# AD9851.net
KiCad netlist of a schematic drawn in Altium Designer
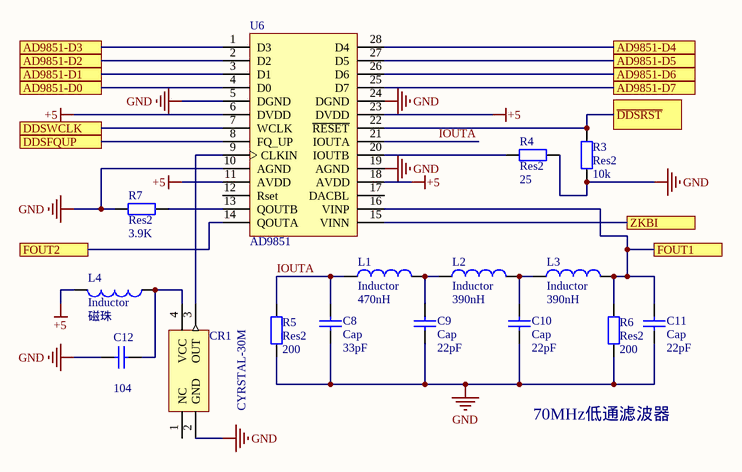
[diagram p0: AD9851电路.SchDoc]

(export (version "E")
  (design (tool "Eeschema 10.0.6"))
  (components
    (comp (ref "C8")
      (value "Cap")
      (footprint "C0805")
      (description "Capacitor")
      (fields (field (name "ALTIUM_VALUE") "33pF") (field (name "PUBLISHER") "Altium Limited"))
      (libsource (lib "基于SMT32的DDS信号源原理图库") (part "Cap"))
    )
    (comp (ref "C9")
      (value "Cap")
      (footprint "C0805")
      (description "Capacitor")
      (fields (field (name "ALTIUM_VALUE") "22pF") (field (name "PUBLISHER") "Altium Limited"))
      (libsource (lib "基于SMT32的DDS信号源原理图库") (part "Cap"))
    )
    (comp (ref "C10")
      (value "Cap")
      (footprint "C0805")
      (description "Capacitor")
      (fields (field (name "ALTIUM_VALUE") "22pF") (field (name "PUBLISHER") "Altium Limited"))
      (libsource (lib "基于SMT32的DDS信号源原理图库") (part "Cap"))
    )
    (comp (ref "C11")
      (value "Cap")
      (footprint "C0805")
      (description "Capacitor")
      (fields (field (name "ALTIUM_VALUE") "22pF") (field (name "PUBLISHER") "Altium Limited"))
      (libsource (lib "基于SMT32的DDS信号源原理图库") (part "Cap"))
    )
    (comp (ref "C12")
      (value "104")
      (footprint "C0805")
      (description "Capacitor")
      (fields (field (name "Comment") "Cap") (field (name "PUBLISHER") "Altium Limited"))
      (libsource (lib "基于SMT32的DDS信号源原理图库") (part "Cap"))
    )
    (comp (ref "CR1")
      (value "CYRSTAL-30M")
      (footprint "CRYSTAL-SMT-5X7")
      (libsource (lib "精华") (part "CYRSTAL-30M"))
    )
    (comp (ref "L1")
      (value "Inductor")
      (footprint "6-0805_N")
      (fields (field (name "ALTIUM_VALUE") "470nH") (field (name "PUBLISHER") "Altium Limited"))
      (libsource (lib "基于SMT32的DDS信号源原理图库") (part "Inductor"))
    )
    (comp (ref "L2")
      (value "Inductor")
      (footprint "6-0805_N")
      (fields (field (name "ALTIUM_VALUE") "390nH") (field (name "PUBLISHER") "Altium Limited"))
      (libsource (lib "基于SMT32的DDS信号源原理图库") (part "Inductor"))
    )
    (comp (ref "L3")
      (value "Inductor")
      (footprint "6-0805_N")
      (fields (field (name "ALTIUM_VALUE") "390nH") (field (name "PUBLISHER") "Altium Limited"))
      (libsource (lib "基于SMT32的DDS信号源原理图库") (part "Inductor"))
    )
    (comp (ref "L4")
      (value "Inductor")
      (footprint "6-0805_N")
      (fields (field (name "ALTIUM_VALUE") "磁珠") (field (name "PUBLISHER") "Altium Limited"))
      (libsource (lib "基于SMT32的DDS信号源原理图库") (part "Inductor"))
    )
    (comp (ref "R3")
      (value "Res2")
      (footprint "6-0805_N")
      (description "Resistor")
      (fields (field (name "ALTIUM_VALUE") "10k") (field (name "PUBLISHER") "Altium Limited"))
      (libsource (lib "") (part "Res2_1"))
    )
    (comp (ref "R4")
      (value "Res2")
      (footprint "6-0805_N")
      (description "Resistor")
      (fields (field (name "ALTIUM_VALUE") "25") (field (name "PUBLISHER") "Altium Limited"))
      (libsource (lib "基于SMT32的DDS信号源原理图库") (part "Res2"))
    )
    (comp (ref "R5")
      (value "Res2")
      (footprint "6-0805_N")
      (description "Resistor")
      (fields (field (name "ALTIUM_VALUE") "200") (field (name "PUBLISHER") "Altium Limited"))
      (libsource (lib "") (part "Res2_1"))
    )
    (comp (ref "R6")
      (value "Res2")
      (footprint "6-0805_N")
      (description "Resistor")
      (fields (field (name "ALTIUM_VALUE") "200") (field (name "PUBLISHER") "Altium Limited"))
      (libsource (lib "") (part "Res2_1"))
    )
    (comp (ref "R7")
      (value "Res2")
      (footprint "6-0805_N")
      (description "Resistor")
      (fields (field (name "ALTIUM_VALUE") "3.9K") (field (name "PUBLISHER") "Altium Limited"))
      (libsource (lib "Miscellaneous Devices") (part "Res2"))
    )
    (comp (ref "U6")
      (value "AD9851")
      (footprint "TSSOP28")
      (libsource (lib "基于SMT32的DDS信号源原理图库") (part "AD9851"))
    )
  )
  (nets
    (net (code "1") (name "+5") (class "Default")
      (node (ref "L4") (pin "2") (pinfunction "2_2") (pintype "passive"))
      (node (ref "U6") (pin "11") (pinfunction "AVDD_11") (pintype "passive"))
      (node (ref "U6") (pin "18") (pinfunction "AVDD_18") (pintype "passive"))
      (node (ref "U6") (pin "23") (pinfunction "DVDD_23") (pintype "passive"))
      (node (ref "U6") (pin "6") (pinfunction "DVDD_6") (pintype "passive"))
    )
    (net (code "2") (name "/AD9851-D0") (class "Default")
      (node (ref "U6") (pin "4") (pinfunction "D0_4") (pintype "passive"))
    )
    (net (code "3") (name "/AD9851-D1") (class "Default")
      (node (ref "U6") (pin "3") (pinfunction "D1_3") (pintype "passive"))
    )
    (net (code "4") (name "/AD9851-D2") (class "Default")
      (node (ref "U6") (pin "2") (pinfunction "D2_2") (pintype "passive"))
    )
    (net (code "5") (name "/AD9851-D3") (class "Default")
      (node (ref "U6") (pin "1") (pinfunction "D3_1") (pintype "passive"))
    )
    (net (code "6") (name "/AD9851-D4") (class "Default")
      (node (ref "U6") (pin "28") (pinfunction "D4_28") (pintype "passive"))
    )
    (net (code "7") (name "/AD9851-D5") (class "Default")
      (node (ref "U6") (pin "27") (pinfunction "D5_27") (pintype "passive"))
    )
    (net (code "8") (name "/AD9851-D6") (class "Default")
      (node (ref "U6") (pin "26") (pinfunction "D6_26") (pintype "passive"))
    )
    (net (code "9") (name "/AD9851-D7") (class "Default")
      (node (ref "U6") (pin "25") (pinfunction "D7_25") (pintype "passive"))
    )
    (net (code "10") (name "/DDSFQUP") (class "Default")
      (node (ref "U6") (pin "8") (pinfunction "FQ_UP_8") (pintype "passive"))
    )
    (net (code "11") (name "/DDSWCLK") (class "Default")
      (node (ref "U6") (pin "7") (pinfunction "WCLK_7") (pintype "passive"))
    )
    (net (code "12") (name "/FOUT1") (class "Default")
      (node (ref "C11") (pin "2") (pinfunction "2_2") (pintype "passive"))
      (node (ref "L3") (pin "2") (pinfunction "2_2") (pintype "passive"))
      (node (ref "R6") (pin "2") (pinfunction "2_2") (pintype "passive"))
      (node (ref "U6") (pin "16") (pinfunction "VINP_16") (pintype "passive"))
    )
    (net (code "13") (name "/FOUT2") (class "Default")
      (node (ref "U6") (pin "14") (pinfunction "QOUTA_14") (pintype "passive"))
    )
    (net (code "14") (name "/IOUTA") (class "Default")
      (node (ref "C8") (pin "2") (pinfunction "2_2") (pintype "passive"))
      (node (ref "L1") (pin "1") (pinfunction "1_1") (pintype "passive"))
      (node (ref "R5") (pin "2") (pinfunction "2_2") (pintype "passive"))
      (node (ref "U6") (pin "21") (pinfunction "IOUTA_21") (pintype "passive"))
    )
    (net (code "15") (name "/ZKBI") (class "Default")
      (node (ref "U6") (pin "15") (pinfunction "VINN_15") (pintype "passive"))
    )
    (net (code "16") (name "/~{DDSRST}") (class "Default")
      (node (ref "R3") (pin "2") (pinfunction "2_2") (pintype "passive"))
      (node (ref "U6") (pin "22") (pinfunction "~{RESET}_22") (pintype "passive"))
    )
    (net (code "17") (name "GND") (class "Default")
      (node (ref "C10") (pin "1") (pinfunction "1_1") (pintype "passive"))
      (node (ref "C11") (pin "1") (pinfunction "1_1") (pintype "passive"))
      (node (ref "C12") (pin "2") (pinfunction "2_2") (pintype "passive"))
      (node (ref "C8") (pin "1") (pinfunction "1_1") (pintype "passive"))
      (node (ref "C9") (pin "1") (pinfunction "1_1") (pintype "passive"))
      (node (ref "CR1") (pin "2") (pinfunction "GND_2") (pintype "power_in"))
      (node (ref "R3") (pin "1") (pinfunction "1_1") (pintype "passive"))
      (node (ref "R4") (pin "2") (pinfunction "2_2") (pintype "passive"))
      (node (ref "R5") (pin "1") (pinfunction "1_1") (pintype "passive"))
      (node (ref "R6") (pin "1") (pinfunction "1_1") (pintype "passive"))
      (node (ref "R7") (pin "2") (pinfunction "2_2") (pintype "passive"))
      (node (ref "U6") (pin "10") (pinfunction "AGND_10") (pintype "passive"))
      (node (ref "U6") (pin "19") (pinfunction "AGND_19") (pintype "passive"))
      (node (ref "U6") (pin "24") (pinfunction "DGND_24") (pintype "passive"))
      (node (ref "U6") (pin "5") (pinfunction "DGND_5") (pintype "passive"))
    )
    (net (code "18") (name "Net-(C9-Pad2)") (class "Default")
      (node (ref "C9") (pin "2") (pinfunction "2_2") (pintype "passive"))
      (node (ref "L1") (pin "2") (pinfunction "2_2") (pintype "passive"))
      (node (ref "L2") (pin "1") (pinfunction "1_1") (pintype "passive"))
    )
    (net (code "19") (name "Net-(C10-Pad2)") (class "Default")
      (node (ref "C10") (pin "2") (pinfunction "2_2") (pintype "passive"))
      (node (ref "L2") (pin "2") (pinfunction "2_2") (pintype "passive"))
      (node (ref "L3") (pin "1") (pinfunction "1_1") (pintype "passive"))
    )
    (net (code "20") (name "Net-(CR1-OUT)") (class "Default")
      (node (ref "CR1") (pin "3") (pinfunction "OUT_3") (pintype "output"))
      (node (ref "U6") (pin "9") (pinfunction "CLKIN_9") (pintype "passive"))
    )
    (net (code "21") (name "Net-(CR1-VCC)") (class "Default")
      (node (ref "C12") (pin "1") (pinfunction "1_1") (pintype "passive"))
      (node (ref "CR1") (pin "4") (pinfunction "VCC_4") (pintype "power_in"))
      (node (ref "L4") (pin "1") (pinfunction "1_1") (pintype "passive"))
    )
    (net (code "22") (name "Net-(U6-IOUTB)") (class "Default")
      (node (ref "R4") (pin "1") (pinfunction "1_1") (pintype "passive"))
      (node (ref "U6") (pin "20") (pinfunction "IOUTB_20") (pintype "passive"))
    )
    (net (code "23") (name "Net-(U6-QOUTB)") (class "Default")
      (node (ref "R7") (pin "1") (pinfunction "1_1") (pintype "passive"))
      (node (ref "U6") (pin "13") (pinfunction "QOUTB_13") (pintype "passive"))
    )
    (net (code "24") (name "unconnected-(CR1-NC-Pad1)") (class "Default")
      (node (ref "CR1") (pin "1") (pinfunction "NC_1") (pintype "passive"))
    )
    (net (code "25") (name "unconnected-(U6-DACBL-Pad17)") (class "Default")
      (node (ref "U6") (pin "17") (pinfunction "DACBL_17") (pintype "passive"))
    )
    (net (code "26") (name "unconnected-(U6-Rset-Pad12)") (class "Default")
      (node (ref "U6") (pin "12") (pinfunction "Rset_12") (pintype "passive"))
    )
  )
)
